# piccontrolissimo.net
KiCad netlist of a schematic drawn in EAGLE
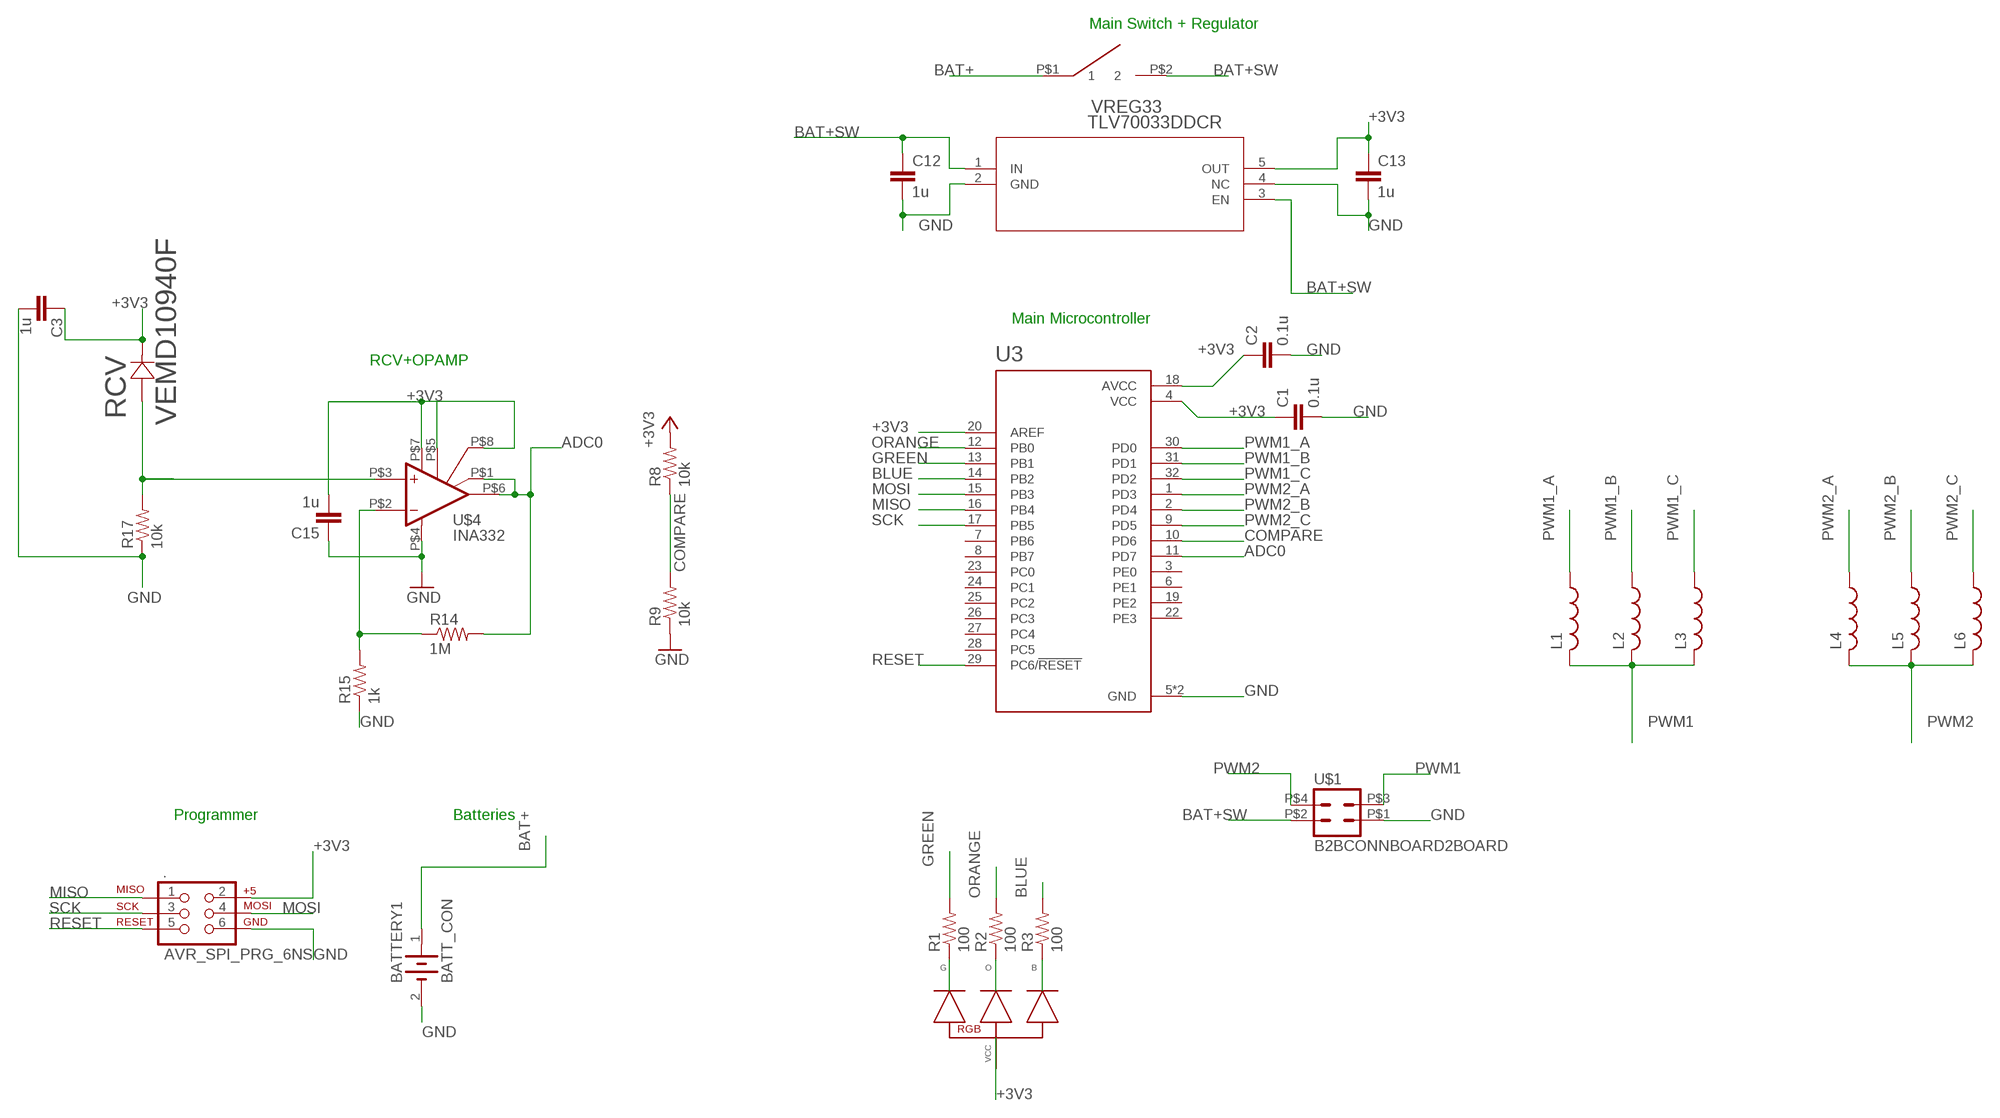
[diagram p0: schematic, sheet 1]

(export (version "E")
  (design (tool "Eeschema 10.0.6"))
  (components
    (comp (ref ".")
      (value "AVR_SPI_PRG_6NS")
      (footprint "eagle-import:2X3-NS")
      (libsource (lib "eagle-import") (part "AVR_SPI_PRG_6NS"))
    )
    (comp (ref "BATTERY1")
      (value "BATT_CON")
      (footprint "eagle-import:2X2BATTCON")
      (libsource (lib "eagle-import") (part "BATT_CON"))
    )
    (comp (ref "C1")
      (value "0.1u")
      (footprint "eagle-import:C0603")
      (libsource (lib "eagle-import") (part "C-EUC0603"))
    )
    (comp (ref "C2")
      (value "0.1u")
      (footprint "eagle-import:C0603")
      (libsource (lib "eagle-import") (part "C-EUC0603"))
    )
    (comp (ref "C3")
      (value "1u")
      (footprint "eagle-import:C0603")
      (libsource (lib "eagle-import") (part "C-EUC0603"))
    )
    (comp (ref "C12")
      (value "1u")
      (footprint "eagle-import:C0603")
      (libsource (lib "eagle-import") (part "C-EUC0603"))
    )
    (comp (ref "C13")
      (value "1u")
      (footprint "eagle-import:C0603")
      (libsource (lib "eagle-import") (part "C-EUC0603"))
    )
    (comp (ref "C15")
      (value "1u")
      (footprint "eagle-import:C0603")
      (libsource (lib "eagle-import") (part "C-EUC0603"))
    )
    (comp (ref "L1")
      (value "L-USL0201")
      (footprint "eagle-import:L0201")
      (libsource (lib "eagle-import") (part "L-USL0201"))
    )
    (comp (ref "L2")
      (value "L-USL0201")
      (footprint "eagle-import:L0201")
      (libsource (lib "eagle-import") (part "L-USL0201"))
    )
    (comp (ref "L3")
      (value "L-USL0201")
      (footprint "eagle-import:L0201")
      (libsource (lib "eagle-import") (part "L-USL0201"))
    )
    (comp (ref "L4")
      (value "L-USL0201")
      (footprint "eagle-import:L0201")
      (libsource (lib "eagle-import") (part "L-USL0201"))
    )
    (comp (ref "L5")
      (value "L-USL0201")
      (footprint "eagle-import:L0201")
      (libsource (lib "eagle-import") (part "L-USL0201"))
    )
    (comp (ref "L6")
      (value "L-USL0201")
      (footprint "eagle-import:L0201")
      (libsource (lib "eagle-import") (part "L-USL0201"))
    )
    (comp (ref "R1")
      (value "100")
      (footprint "eagle-import:R0603")
      (libsource (lib "eagle-import") (part "R-US_R0603"))
    )
    (comp (ref "R2")
      (value "100")
      (footprint "eagle-import:R0603")
      (libsource (lib "eagle-import") (part "R-US_R0603"))
    )
    (comp (ref "R3")
      (value "100")
      (footprint "eagle-import:R0603")
      (libsource (lib "eagle-import") (part "R-US_R0603"))
    )
    (comp (ref "R8")
      (value "10k")
      (footprint "eagle-import:R0603")
      (libsource (lib "eagle-import") (part "R-US_R0603"))
    )
    (comp (ref "R9")
      (value "10k")
      (footprint "eagle-import:R0603")
      (libsource (lib "eagle-import") (part "R-US_R0603"))
    )
    (comp (ref "R14")
      (value "1M")
      (footprint "eagle-import:R0603")
      (libsource (lib "eagle-import") (part "R-US_R0603"))
    )
    (comp (ref "R15")
      (value "1k")
      (footprint "eagle-import:R0603")
      (libsource (lib "eagle-import") (part "R-US_R0603"))
    )
    (comp (ref "R17")
      (value "10k")
      (footprint "eagle-import:R0603")
      (libsource (lib "eagle-import") (part "R-US_R0603"))
    )
    (comp (ref "RCV")
      (value "VEMD10940F")
      (footprint "eagle-import:VEMD10940F")
      (libsource (lib "eagle-import") (part "VEMD10940F"))
    )
    (comp (ref "RGB1")
      (value "RGBLED")
      (footprint "eagle-import:RGBLED")
      (libsource (lib "eagle-import") (part "RGBLED"))
    )
    (comp (ref "SWITCH")
      (value "DIP01")
      (footprint "eagle-import:DIP01")
      (libsource (lib "eagle-import") (part "DIP01"))
    )
    (comp (ref "U$1")
      (value "B2BCONNBOARD2BOARD")
      (footprint "eagle-import:B2B")
      (libsource (lib "eagle-import") (part "B2BCONNBOARD2BOARD"))
    )
    (comp (ref "U$4")
      (value "INA332")
      (footprint "eagle-import:INA332")
      (libsource (lib "eagle-import") (part "INA332"))
    )
    (comp (ref "U3")
      (value "ATMEGA328PB-AUR")
      (footprint "eagle-import:QFP80P900X900X120-32N")
      (fields (field (name "DIGI-KEY_PART_NUMBER") "ATMEGA328PB-AURCT-ND") (field (name "MF") "Microchip"))
      (libsource (lib "eagle-import") (part "ATMEGA328PB-AUR"))
    )
    (comp (ref "VREG33")
      (value "TLV70033DDCR")
      (footprint "eagle-import:DDC5")
      (libsource (lib "eagle-import") (part "TLV70033DDCR"))
    )
  )
  (nets
    (net (code "1") (name "+3V3") (class "Default")
      (node (ref ".") (pin "2") (pinfunction "2_2") (pintype "passive"))
      (node (ref "C1") (pin "1") (pinfunction "1_1") (pintype "passive"))
      (node (ref "C13") (pin "1") (pinfunction "1_1") (pintype "passive"))
      (node (ref "C15") (pin "2") (pinfunction "2_2") (pintype "passive"))
      (node (ref "C2") (pin "1") (pinfunction "1_1") (pintype "passive"))
      (node (ref "C3") (pin "1") (pinfunction "1_1") (pintype "passive"))
      (node (ref "R8") (pin "2") (pinfunction "2_2") (pintype "passive"))
      (node (ref "RCV") (pin "CA-") (pinfunction "CA-_CA-") (pintype "passive"))
      (node (ref "RGB1") (pin "VCC") (pinfunction "VCC_VCC") (pintype "power_in"))
      (node (ref "U$4") (pin "P$5") (pinfunction "VREF_P$5") (pintype "passive"))
      (node (ref "U$4") (pin "P$7") (pinfunction "V+_P$7") (pintype "power_in"))
      (node (ref "U$4") (pin "P$8") (pinfunction "SHDN_P$8") (pintype "passive"))
      (node (ref "U3") (pin "18") (pinfunction "AVCC_18") (pintype "power_in"))
      (node (ref "U3") (pin "20") (pinfunction "AREF_20") (pintype "input"))
      (node (ref "U3") (pin "4") (pinfunction "VCC_4") (pintype "power_in"))
      (node (ref "VREG33") (pin "5") (pinfunction "OUT_5") (pintype "output"))
    )
    (net (code "2") (name "/ADC0") (class "Default")
      (node (ref "R14") (pin "2") (pinfunction "2_2") (pintype "passive"))
      (node (ref "U$4") (pin "P$1") (pinfunction "RG_P$1") (pintype "passive"))
      (node (ref "U$4") (pin "P$6") (pinfunction "OUT_P$6") (pintype "output"))
      (node (ref "U3") (pin "11") (pinfunction "PD7_11") (pintype "bidirectional"))
    )
    (net (code "3") (name "/BAT+") (class "Default")
      (node (ref "BATTERY1") (pin "1") (pinfunction "+_1") (pintype "passive"))
      (node (ref "SWITCH") (pin "P$1") (pinfunction "1_P$1") (pintype "bidirectional"))
    )
    (net (code "4") (name "/BAT+SW") (class "Default")
      (node (ref "C12") (pin "1") (pinfunction "1_1") (pintype "passive"))
      (node (ref "SWITCH") (pin "P$2") (pinfunction "2_P$2") (pintype "bidirectional"))
      (node (ref "U$1") (pin "P$2") (pinfunction "2_P$2") (pintype "passive"))
      (node (ref "VREG33") (pin "1") (pinfunction "IN_1") (pintype "input"))
      (node (ref "VREG33") (pin "3") (pinfunction "EN_3") (pintype "passive"))
    )
    (net (code "5") (name "/BLUE") (class "Default")
      (node (ref "R3") (pin "2") (pinfunction "2_2") (pintype "passive"))
      (node (ref "U3") (pin "14") (pinfunction "PB2_14") (pintype "bidirectional"))
    )
    (net (code "6") (name "/COMPARE") (class "Default")
      (node (ref "R8") (pin "1") (pinfunction "1_1") (pintype "passive"))
      (node (ref "R9") (pin "2") (pinfunction "2_2") (pintype "passive"))
      (node (ref "U3") (pin "10") (pinfunction "PD6_10") (pintype "bidirectional"))
    )
    (net (code "7") (name "/GREEN") (class "Default")
      (node (ref "R1") (pin "2") (pinfunction "2_2") (pintype "passive"))
      (node (ref "U3") (pin "13") (pinfunction "PB1_13") (pintype "bidirectional"))
    )
    (net (code "8") (name "/MISO") (class "Default")
      (node (ref ".") (pin "1") (pinfunction "1_1") (pintype "passive"))
      (node (ref "U3") (pin "16") (pinfunction "PB4_16") (pintype "bidirectional"))
    )
    (net (code "9") (name "/MOSI") (class "Default")
      (node (ref ".") (pin "4") (pinfunction "4_4") (pintype "passive"))
      (node (ref "U3") (pin "15") (pinfunction "PB3_15") (pintype "bidirectional"))
    )
    (net (code "10") (name "/ORANGE") (class "Default")
      (node (ref "R2") (pin "2") (pinfunction "2_2") (pintype "passive"))
      (node (ref "U3") (pin "12") (pinfunction "PB0_12") (pintype "bidirectional"))
    )
    (net (code "11") (name "/PWM1") (class "Default")
      (node (ref "L1") (pin "2") (pinfunction "2_2") (pintype "passive"))
      (node (ref "L2") (pin "2") (pinfunction "2_2") (pintype "passive"))
      (node (ref "L3") (pin "2") (pinfunction "2_2") (pintype "passive"))
      (node (ref "U$1") (pin "P$3") (pinfunction "3_P$3") (pintype "passive"))
    )
    (net (code "12") (name "/PWM1_A") (class "Default")
      (node (ref "L1") (pin "1") (pinfunction "1_1") (pintype "passive"))
      (node (ref "U3") (pin "30") (pinfunction "PD0_30") (pintype "bidirectional"))
    )
    (net (code "13") (name "/PWM1_B") (class "Default")
      (node (ref "L2") (pin "1") (pinfunction "1_1") (pintype "passive"))
      (node (ref "U3") (pin "31") (pinfunction "PD1_31") (pintype "bidirectional"))
    )
    (net (code "14") (name "/PWM1_C") (class "Default")
      (node (ref "L3") (pin "1") (pinfunction "1_1") (pintype "passive"))
      (node (ref "U3") (pin "32") (pinfunction "PD2_32") (pintype "bidirectional"))
    )
    (net (code "15") (name "/PWM2") (class "Default")
      (node (ref "L4") (pin "2") (pinfunction "2_2") (pintype "passive"))
      (node (ref "L5") (pin "2") (pinfunction "2_2") (pintype "passive"))
      (node (ref "L6") (pin "2") (pinfunction "2_2") (pintype "passive"))
      (node (ref "U$1") (pin "P$4") (pinfunction "4_P$4") (pintype "passive"))
    )
    (net (code "16") (name "/PWM2_A") (class "Default")
      (node (ref "L4") (pin "1") (pinfunction "1_1") (pintype "passive"))
      (node (ref "U3") (pin "1") (pinfunction "PD3_1") (pintype "bidirectional"))
    )
    (net (code "17") (name "/PWM2_B") (class "Default")
      (node (ref "L5") (pin "1") (pinfunction "1_1") (pintype "passive"))
      (node (ref "U3") (pin "2") (pinfunction "PD4_2") (pintype "bidirectional"))
    )
    (net (code "18") (name "/PWM2_C") (class "Default")
      (node (ref "L6") (pin "1") (pinfunction "1_1") (pintype "passive"))
      (node (ref "U3") (pin "9") (pinfunction "PD5_9") (pintype "bidirectional"))
    )
    (net (code "19") (name "/RESET") (class "Default")
      (node (ref ".") (pin "5") (pinfunction "5_5") (pintype "passive"))
      (node (ref "U3") (pin "29") (pinfunction "PC6/~{RESET}_29") (pintype "bidirectional"))
    )
    (net (code "20") (name "/SCK") (class "Default")
      (node (ref ".") (pin "3") (pinfunction "3_3") (pintype "passive"))
      (node (ref "U3") (pin "17") (pinfunction "PB5_17") (pintype "bidirectional"))
    )
    (net (code "21") (name "GND") (class "Default")
      (node (ref ".") (pin "6") (pinfunction "6_6") (pintype "passive"))
      (node (ref "BATTERY1") (pin "2") (pinfunction "-_2") (pintype "passive"))
      (node (ref "C1") (pin "2") (pinfunction "2_2") (pintype "passive"))
      (node (ref "C12") (pin "2") (pinfunction "2_2") (pintype "passive"))
      (node (ref "C13") (pin "2") (pinfunction "2_2") (pintype "passive"))
      (node (ref "C15") (pin "1") (pinfunction "1_1") (pintype "passive"))
      (node (ref "C2") (pin "2") (pinfunction "2_2") (pintype "passive"))
      (node (ref "C3") (pin "2") (pinfunction "2_2") (pintype "passive"))
      (node (ref "R15") (pin "1") (pinfunction "1_1") (pintype "passive"))
      (node (ref "R17") (pin "1") (pinfunction "1_1") (pintype "passive"))
      (node (ref "R9") (pin "1") (pinfunction "1_1") (pintype "passive"))
      (node (ref "U$1") (pin "P$1") (pinfunction "1_P$1") (pintype "passive"))
      (node (ref "U$4") (pin "P$4") (pinfunction "V-_P$4") (pintype "power_in"))
      (node (ref "U3") (pin "21") (pinfunction "GND_21") (pintype "power_in"))
      (node (ref "U3") (pin "5") (pinfunction "GND_5") (pintype "power_in"))
      (node (ref "VREG33") (pin "2") (pinfunction "GND_2") (pintype "power_in"))
      (node (ref "VREG33") (pin "4") (pinfunction "NC_4") (pintype "passive"))
    )
    (net (code "22") (name "Net-(R1-Pad1)") (class "Default")
      (node (ref "R1") (pin "1") (pinfunction "1_1") (pintype "passive"))
      (node (ref "RGB1") (pin "GREEN") (pinfunction "GREEN_GREEN") (pintype "input"))
    )
    (net (code "23") (name "Net-(R2-Pad1)") (class "Default")
      (node (ref "R2") (pin "1") (pinfunction "1_1") (pintype "passive"))
      (node (ref "RGB1") (pin "ORANGE") (pinfunction "ORANGE_ORANGE") (pintype "input"))
    )
    (net (code "24") (name "Net-(R3-Pad1)") (class "Default")
      (node (ref "R3") (pin "1") (pinfunction "1_1") (pintype "passive"))
      (node (ref "RGB1") (pin "BLUE") (pinfunction "BLUE_BLUE") (pintype "input"))
    )
    (net (code "25") (name "Net-(U$4-+IN)") (class "Default")
      (node (ref "R17") (pin "2") (pinfunction "2_2") (pintype "passive"))
      (node (ref "RCV") (pin "AN+") (pinfunction "AN+_AN+") (pintype "passive"))
      (node (ref "U$4") (pin "P$3") (pinfunction "+IN_P$3") (pintype "input"))
    )
    (net (code "26") (name "Net-(U$4--IN)") (class "Default")
      (node (ref "R14") (pin "1") (pinfunction "1_1") (pintype "passive"))
      (node (ref "R15") (pin "2") (pinfunction "2_2") (pintype "passive"))
      (node (ref "U$4") (pin "P$2") (pinfunction "-IN_P$2") (pintype "input"))
    )
    (net (code "27") (name "unconnected-(U3-PB6-Pad7)") (class "Default")
      (node (ref "U3") (pin "7") (pinfunction "PB6_7") (pintype "bidirectional"))
    )
    (net (code "28") (name "unconnected-(U3-PB7-Pad8)") (class "Default")
      (node (ref "U3") (pin "8") (pinfunction "PB7_8") (pintype "bidirectional"))
    )
    (net (code "29") (name "unconnected-(U3-PC0-Pad23)") (class "Default")
      (node (ref "U3") (pin "23") (pinfunction "PC0_23") (pintype "bidirectional"))
    )
    (net (code "30") (name "unconnected-(U3-PC1-Pad24)") (class "Default")
      (node (ref "U3") (pin "24") (pinfunction "PC1_24") (pintype "bidirectional"))
    )
    (net (code "31") (name "unconnected-(U3-PC2-Pad25)") (class "Default")
      (node (ref "U3") (pin "25") (pinfunction "PC2_25") (pintype "bidirectional"))
    )
    (net (code "32") (name "unconnected-(U3-PC3-Pad26)") (class "Default")
      (node (ref "U3") (pin "26") (pinfunction "PC3_26") (pintype "bidirectional"))
    )
    (net (code "33") (name "unconnected-(U3-PC4-Pad27)") (class "Default")
      (node (ref "U3") (pin "27") (pinfunction "PC4_27") (pintype "bidirectional"))
    )
    (net (code "34") (name "unconnected-(U3-PC5-Pad28)") (class "Default")
      (node (ref "U3") (pin "28") (pinfunction "PC5_28") (pintype "bidirectional"))
    )
    (net (code "35") (name "unconnected-(U3-PE0-Pad3)") (class "Default")
      (node (ref "U3") (pin "3") (pinfunction "PE0_3") (pintype "bidirectional"))
    )
    (net (code "36") (name "unconnected-(U3-PE1-Pad6)") (class "Default")
      (node (ref "U3") (pin "6") (pinfunction "PE1_6") (pintype "bidirectional"))
    )
    (net (code "37") (name "unconnected-(U3-PE2-Pad19)") (class "Default")
      (node (ref "U3") (pin "19") (pinfunction "PE2_19") (pintype "bidirectional"))
    )
    (net (code "38") (name "unconnected-(U3-PE3-Pad22)") (class "Default")
      (node (ref "U3") (pin "22") (pinfunction "PE3_22") (pintype "bidirectional"))
    )
  )
)
